# PWMFanController.net
KiCad netlist of a schematic drawn in EasyEDA Pro
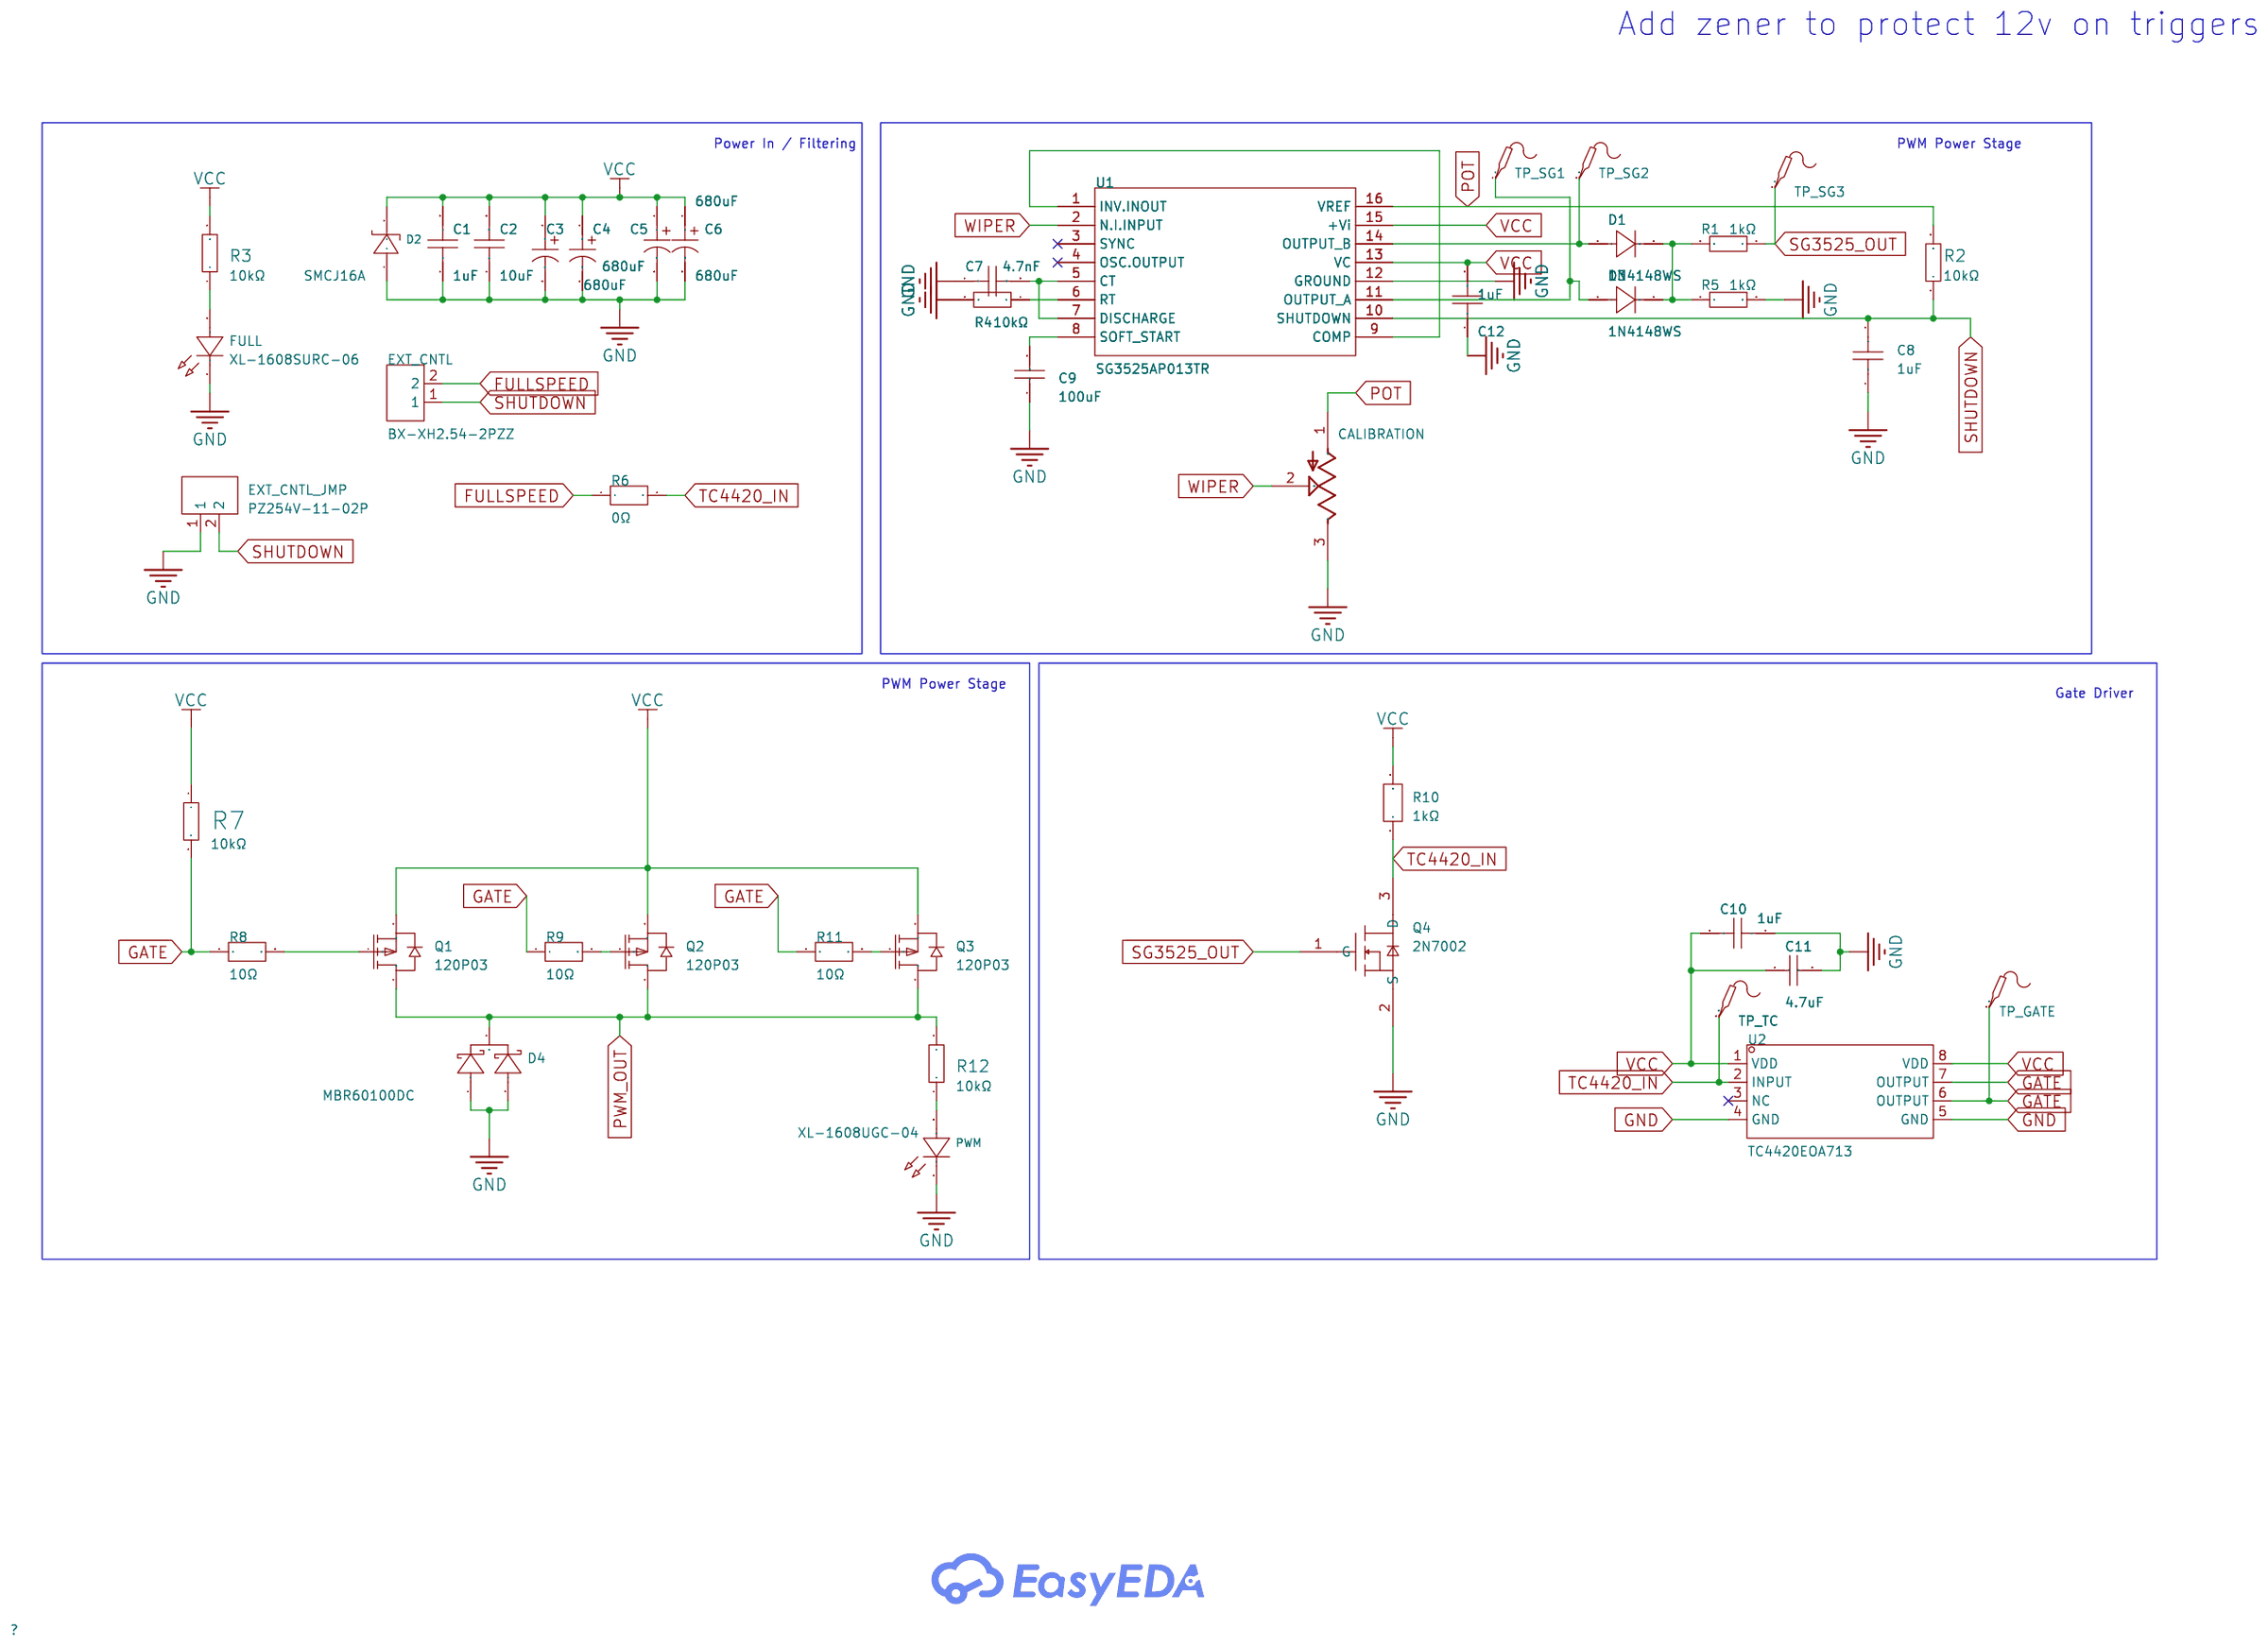
[diagram p0: schematic sheet]

(export (version "E")
  (design (tool "Eeschema 10.0.6"))
  (components
    (comp (ref "C1")
      (value "1uF")
      (footprint "easyedapro:C0805")
      (fields
        (field (name "Manufacturer Part") "GCM21BR7YA105KA55L")
        (field (name "Manufacturer") "muRata(村田)")
      )
      (libsource (lib "easyedapro") (part "GCM21BR7YA105KA55L"))
    )
    (comp (ref "C2")
      (value "10uF")
      (footprint "easyedapro:C0805")
      (fields
        (field (name "Manufacturer Part") "GRM21BC8YA106KE11L")
        (field (name "Manufacturer") "muRata(村田)")
      )
      (libsource (lib "easyedapro") (part "GRM21BC8YA106KE11L"))
    )
    (comp (ref "C3")
      (value "680uF")
      (footprint "easyedapro:CAP-SMD_BD10.0-L10.3-W10.3-FD-LS11.0_H12.0")
      (fields (field (name "Manufacturer Part") "MA35V680M10X13") (field (name "Manufacturer") "JIERR(捷而瑞)"))
      (libsource (lib "easyedapro") (part "MA35V680M10X13"))
    )
    (comp (ref "C4")
      (value "680uF")
      (footprint "easyedapro:CAP-SMD_BD10.0-L10.3-W10.3-FD-LS11.0_H12.0")
      (fields (field (name "Manufacturer Part") "MA35V680M10X13") (field (name "Manufacturer") "JIERR(捷而瑞)"))
      (libsource (lib "easyedapro") (part "MA35V680M10X13"))
    )
    (comp (ref "C5")
      (value "680uF")
      (footprint "easyedapro:CAP-SMD_BD10.0-L10.3-W10.3-FD-LS11.0_H12.0")
      (fields (field (name "Manufacturer Part") "MA35V680M10X13") (field (name "Manufacturer") "JIERR(捷而瑞)"))
      (libsource (lib "easyedapro") (part "MA35V680M10X13"))
    )
    (comp (ref "C6")
      (value "680uF")
      (footprint "easyedapro:CAP-SMD_BD10.0-L10.3-W10.3-FD-LS11.0_H12.0")
      (fields (field (name "Manufacturer Part") "MA35V680M10X13") (field (name "Manufacturer") "JIERR(捷而瑞)"))
      (libsource (lib "easyedapro") (part "MA35V680M10X13"))
    )
    (comp (ref "C7")
      (value "4.7nF")
      (footprint "easyedapro:C0603")
      (fields
        (field (name "Manufacturer Part") "CC0603JRNPO9BN472")
        (field (name "Manufacturer") "YAGEO(国巨)")
      )
      (libsource (lib "easyedapro") (part "CC0603JRNPO9BN472"))
    )
    (comp (ref "C8")
      (value "1uF")
      (footprint "easyedapro:C0603")
      (description "Capacitance:1uF Tolerance:±10% Tolerance:±10% Voltage Rating:25V Temperature Coefficient:X7R")
      (fields
        (field (name "Manufacturer Part") "HGC0603R7105K250NTHJ")
        (field (name "Manufacturer") "Chinocera(华瓷)")
      )
      (libsource (lib "easyedapro") (part "HGC0603R7105K250NTHJ"))
    )
    (comp (ref "C9")
      (value "100uF")
      (footprint "easyedapro:C1206")
      (description "Capacitance:100uF Tolerance:±20% Tolerance:±20% Voltage Rating:6.3V Temperature Coefficient:X5R")
      (fields
        (field (name "Manufacturer Part") "CL31A107MQHNNNE")
        (field (name "Manufacturer") "SAMSUNG(三星)")
      )
      (libsource (lib "easyedapro") (part "CL31A107MQHNNNE"))
    )
    (comp (ref "C10")
      (value "1uF")
      (footprint "easyedapro:C0603")
      (description "Capacitance:1uF Tolerance:±10% Tolerance:±10% Voltage Rating:35V Temperature Coefficient:X7R")
      (fields (field (name "Manufacturer Part") "CGA3E1X7R1V105KT000N") (field (name "Manufacturer") "TDK"))
      (libsource (lib "easyedapro") (part "CGA3E1X7R1V105KT000N"))
    )
    (comp (ref "C11")
      (value "4.7uF")
      (footprint "easyedapro:C0603")
      (description "Capacitance:4.7uF Tolerance:±10% Tolerance:±10% Voltage Rating:16V Temperature Coefficient:X5R")
      (fields
        (field (name "Manufacturer Part") "EMK107ABJ475KA-T")
        (field (name "Manufacturer") "TAIYO YUDEN(太诱)")
      )
      (libsource (lib "easyedapro") (part "EMK107ABJ475KA-T"))
    )
    (comp (ref "C12")
      (value "1uF")
      (footprint "easyedapro:C0603")
      (description "Capacitance:1uF Tolerance:±10% Tolerance:±10% Voltage Rating:25V Temperature Coefficient:X7R")
      (fields
        (field (name "Manufacturer Part") "HGC0603R7105K250NTHJ")
        (field (name "Manufacturer") "Chinocera(华瓷)")
      )
      (libsource (lib "easyedapro") (part "HGC0603R7105K250NTHJ"))
    )
    (comp (ref "CALIBRATION")
      (value "10kΩ")
      (description "Resistance: Tolerance:±10% Tolerance:±10%")
      (fields (field (name "Manufacturer Part") "3362P-1-103") (field (name "Manufacturer") "BOCHEN(博晨)"))
      (libsource (lib "easyedapro") (part "3362P-1-253LF_3362P-1-253LF_"))
    )
    (comp (ref "D1")
      (value "1N4148WS")
      (footprint "easyedapro:SOD-323_L1.8-W1.3-LS2.5-RD")
      (fields (field (name "Manufacturer") "JSMSEMI(杰盛微)"))
      (libsource (lib "easyedapro") (part "1N4148WS_C917117"))
    )
    (comp (ref "D2")
      (value "SMCJ16A")
      (footprint "easyedapro:SMC_L7.1-W6.2-LS8.1-R-RD")
      (fields (field (name "Manufacturer") "RUILON(瑞隆源)"))
      (libsource (lib "easyedapro") (part "SMCJ16A"))
    )
    (comp (ref "D3")
      (value "1N4148WS")
      (footprint "easyedapro:SOD-323_L1.8-W1.3-LS2.5-RD")
      (fields (field (name "Manufacturer") "JSMSEMI(杰盛微)"))
      (libsource (lib "easyedapro") (part "1N4148WS_C917117"))
    )
    (comp (ref "D4")
      (value "MBR60100DC")
      (fields (field (name "Manufacturer") "YFW(佑风微)"))
      (libsource (lib "easyedapro") (part "SBDB40100TCTB"))
    )
    (comp (ref "EXT_CNTL")
      (value "BX-XH2.54-2PZZ")
      (footprint "easyedapro:CONN-TH_2P-P2.50_BX-XH2.54-2PZZ")
      (fields (field (name "Manufacturer") "Bossie(博锡)"))
      (libsource (lib "easyedapro") (part "BX-XH2.54-2PZZ"))
    )
    (comp (ref "EXT_CNTL_JMP")
      (value "PZ254V-11-02P")
      (footprint "easyedapro:HDR-TH_2P-P2.54-V-M")
      (fields (field (name "Manufacturer") "XFCN(兴飞)"))
      (libsource (lib "easyedapro") (part "PZ254V-11-02P"))
    )
    (comp (ref "FULL")
      (value "XL-1608SURC-06")
      (footprint "easyedapro:LED0603-RD_RED")
      (fields (field (name "Manufacturer") "XINGLIGHT(成兴光)"))
      (libsource (lib "easyedapro") (part "XL-1608SURC-06"))
    )
    (comp (ref "PWM")
      (value "XL-1608UGC-04")
      (footprint "easyedapro:LED0603-RD_GREEN")
      (fields (field (name "Manufacturer") "XINGLIGHT(成兴光)"))
      (libsource (lib "easyedapro") (part "XL-1608UGC-04"))
    )
    (comp (ref "Q1")
      (value "120P03")
      (footprint "easyedapro:TO-252-2_L6.6-W6.1-P4.57-LS9.9-BR-CW")
      (fields (field (name "Manufacturer") "HL(富海微)"))
      (libsource (lib "easyedapro") (part "120P03"))
    )
    (comp (ref "Q2")
      (value "120P03")
      (footprint "easyedapro:TO-252-2_L6.6-W6.1-P4.57-LS9.9-BR-CW")
      (fields (field (name "Manufacturer") "HL(富海微)"))
      (libsource (lib "easyedapro") (part "120P03"))
    )
    (comp (ref "Q3")
      (value "120P03")
      (footprint "easyedapro:TO-252-2_L6.6-W6.1-P4.57-LS9.9-BR-CW")
      (fields (field (name "Manufacturer") "HL(富海微)"))
      (libsource (lib "easyedapro") (part "120P03"))
    )
    (comp (ref "Q4")
      (value "2N7002")
      (footprint "easyedapro:SOT-23-3_L2.9-W1.3-P1.90-LS2.4-BR")
      (fields (field (name "Manufacturer") "JSMSEMI(杰盛微)"))
      (libsource (lib "easyedapro") (part "2N7002_C916396"))
    )
    (comp (ref "R1")
      (value "1kΩ")
      (footprint "easyedapro:R0603")
      (fields
        (field (name "Manufacturer Part") "0603WAF1001T5E")
        (field (name "Manufacturer") "UNI-ROYAL(厚声)")
      )
      (libsource (lib "easyedapro") (part "0603WAF1001T5E"))
    )
    (comp (ref "R2")
      (value "10kΩ")
      (footprint "easyedapro:R0603")
      (fields
        (field (name "Manufacturer Part") "0603WAF1002T5E")
        (field (name "Manufacturer") "UNI-ROYAL(厚声)")
      )
      (libsource (lib "easyedapro") (part "0603WAF1002T5E"))
    )
    (comp (ref "R3")
      (value "10kΩ")
      (footprint "easyedapro:R0603")
      (fields
        (field (name "Manufacturer Part") "0603WAF1002T5E")
        (field (name "Manufacturer") "UNI-ROYAL(厚声)")
      )
      (libsource (lib "easyedapro") (part "0603WAF1002T5E"))
    )
    (comp (ref "R4")
      (value "10kΩ")
      (footprint "easyedapro:R0603")
      (fields
        (field (name "Manufacturer Part") "0603WAF1002T5E")
        (field (name "Manufacturer") "UNI-ROYAL(厚声)")
      )
      (libsource (lib "easyedapro") (part "0603WAF1002T5E"))
    )
    (comp (ref "R5")
      (value "1kΩ")
      (footprint "easyedapro:R0603")
      (fields
        (field (name "Manufacturer Part") "0603WAF1001T5E")
        (field (name "Manufacturer") "UNI-ROYAL(厚声)")
      )
      (libsource (lib "easyedapro") (part "0603WAF1001T5E"))
    )
    (comp (ref "R6")
      (value "0Ω")
      (footprint "easyedapro:R1210")
      (fields (field (name "Manufacturer Part") "FRC1210F0000TS") (field (name "Manufacturer") "FOJAN(富捷)"))
      (libsource (lib "easyedapro") (part "FRC1210F0000TS"))
    )
    (comp (ref "R7")
      (value "10kΩ")
      (footprint "easyedapro:R0603")
      (fields
        (field (name "Manufacturer Part") "0603WAF1002T5E")
        (field (name "Manufacturer") "UNI-ROYAL(厚声)")
      )
      (libsource (lib "easyedapro") (part "0603WAF1002T5E"))
    )
    (comp (ref "R8")
      (value "10Ω")
      (footprint "easyedapro:R0805")
      (fields
        (field (name "Manufacturer Part") "AS05W2J0100T5E")
        (field (name "Manufacturer") "UNI-ROYAL(厚声)")
      )
      (libsource (lib "easyedapro") (part "AS05W3J0100T5E"))
    )
    (comp (ref "R9")
      (value "10Ω")
      (footprint "easyedapro:R0805")
      (fields
        (field (name "Manufacturer Part") "AS05W2J0100T5E")
        (field (name "Manufacturer") "UNI-ROYAL(厚声)")
      )
      (libsource (lib "easyedapro") (part "AS05W3J0100T5E"))
    )
    (comp (ref "R10")
      (value "1kΩ")
      (footprint "easyedapro:R1210")
      (fields (field (name "Manufacturer Part") "FRC1210J102TS") (field (name "Manufacturer") "FOJAN(富捷)"))
      (libsource (lib "easyedapro") (part "FRC1210J102TS"))
    )
    (comp (ref "R11")
      (value "10Ω")
      (footprint "easyedapro:R0805")
      (fields
        (field (name "Manufacturer Part") "AS05W2J0100T5E")
        (field (name "Manufacturer") "UNI-ROYAL(厚声)")
      )
      (libsource (lib "easyedapro") (part "AS05W3J0100T5E"))
    )
    (comp (ref "R12")
      (value "10kΩ")
      (footprint "easyedapro:R0603")
      (fields
        (field (name "Manufacturer Part") "0603WAF1002T5E")
        (field (name "Manufacturer") "UNI-ROYAL(厚声)")
      )
      (libsource (lib "easyedapro") (part "0603WAF1002T5E"))
    )
    (comp (ref "TP_GATE")
      (value "~")
      (footprint "easyedapro:Test-Point-0.5mm")
      (description "Test Point 测试点")
      (libsource (lib "easyedapro") (part "Test-Point"))
    )
    (comp (ref "TP_SG1")
      (value "~")
      (footprint "easyedapro:Test-Point-0.5mm")
      (description "Test Point 测试点")
      (libsource (lib "easyedapro") (part "Test-Point"))
    )
    (comp (ref "TP_SG2")
      (value "~")
      (footprint "easyedapro:Test-Point-0.5mm")
      (description "Test Point 测试点")
      (libsource (lib "easyedapro") (part "Test-Point"))
    )
    (comp (ref "TP_SG3")
      (value "~")
      (footprint "easyedapro:Test-Point-0.5mm")
      (description "Test Point 测试点")
      (libsource (lib "easyedapro") (part "Test-Point"))
    )
    (comp (ref "TP_TC")
      (value "~")
      (footprint "easyedapro:Test-Point-0.5mm")
      (description "Test Point 测试点")
      (libsource (lib "easyedapro") (part "Test-Point"))
    )
    (comp (ref "U1")
      (value "SG3525AP013TR")
      (footprint "easyedapro:SOIC-16_L9.9-W3.9-P1.27-LS6.0-BL")
      (fields (field (name "Manufacturer") "ST(意法半导体)"))
      (libsource (lib "easyedapro") (part "SG3525AP013TR"))
    )
    (comp (ref "U2")
      (value "TC4420EOA713")
      (footprint "easyedapro:SOIC-8_L5.0-W4.0-P1.27-LS6.0-BL")
      (fields (field (name "Manufacturer") "MICROCHIP(美国微芯)"))
      (libsource (lib "easyedapro") (part "TC4420EOA713"))
    )
  )
  (nets
    (net (code "1") (name "FULLSPEED") (class "Default")
      (node (ref "EXT_CNTL") (pin "2") (pinfunction "2_2") (pintype "unspecified"))
      (node (ref "R6") (pin "1") (pinfunction "1_1") (pintype "unspecified"))
    )
    (net (code "2") (name "GATE") (class "Default")
      (node (ref "R11") (pin "1") (pinfunction "1_1") (pintype "unspecified"))
      (node (ref "R7") (pin "2") (pinfunction "2_2") (pintype "input"))
      (node (ref "R8") (pin "1") (pinfunction "1_1") (pintype "unspecified"))
      (node (ref "R9") (pin "1") (pinfunction "1_1") (pintype "unspecified"))
      (node (ref "TP_GATE") (pin "1") (pinfunction "1_1") (pintype "unspecified"))
      (node (ref "U2") (pin "6") (pinfunction "OUTPUT_6") (pintype "unspecified"))
      (node (ref "U2") (pin "7") (pinfunction "OUTPUT_7") (pintype "unspecified"))
    )
    (net (code "3") (name "GND") (class "Default")
      (node (ref "C1") (pin "1") (pinfunction "1_1") (pintype "unspecified"))
      (node (ref "C10") (pin "1") (pinfunction "1_1") (pintype "unspecified"))
      (node (ref "C11") (pin "2") (pinfunction "2_2") (pintype "input"))
      (node (ref "C12") (pin "1") (pinfunction "1_1") (pintype "unspecified"))
      (node (ref "C2") (pin "1") (pinfunction "1_1") (pintype "unspecified"))
      (node (ref "C3") (pin "2") (pinfunction "2_2") (pintype "input"))
      (node (ref "C4") (pin "2") (pinfunction "2_2") (pintype "input"))
      (node (ref "C5") (pin "2") (pinfunction "2_2") (pintype "input"))
      (node (ref "C6") (pin "2") (pinfunction "2_2") (pintype "input"))
      (node (ref "C7") (pin "1") (pinfunction "1_1") (pintype "input"))
      (node (ref "C8") (pin "1") (pinfunction "1_1") (pintype "unspecified"))
      (node (ref "C9") (pin "1") (pinfunction "1_1") (pintype "input"))
      (node (ref "CALIBRATION") (pin "3") (pinfunction "CW_3") (pintype "unspecified"))
      (node (ref "D2") (pin "1") (pinfunction "A_1") (pintype "input"))
      (node (ref "D4") (pin "1") (pinfunction "A_1") (pintype "unspecified"))
      (node (ref "D4") (pin "3") (pinfunction "A_3") (pintype "unspecified"))
      (node (ref "EXT_CNTL_JMP") (pin "1") (pinfunction "1_1") (pintype "unspecified"))
      (node (ref "FULL") (pin "1") (pinfunction "K_1") (pintype "unspecified"))
      (node (ref "PWM") (pin "1") (pinfunction "K_1") (pintype "input"))
      (node (ref "Q4") (pin "2") (pinfunction "S_2") (pintype "unspecified"))
      (node (ref "R4") (pin "2") (pinfunction "2_2") (pintype "input"))
      (node (ref "R5") (pin "2") (pinfunction "2_2") (pintype "input"))
      (node (ref "U1") (pin "12") (pinfunction "GROUND_12") (pintype "unspecified"))
      (node (ref "U2") (pin "4") (pinfunction "GND_4") (pintype "unspecified"))
      (node (ref "U2") (pin "5") (pinfunction "GND_5") (pintype "unspecified"))
    )
    (net (code "4") (name "Net-(D1-A)") (class "Default")
      (node (ref "D1") (pin "2") (pinfunction "A_2") (pintype "unspecified"))
      (node (ref "TP_SG2") (pin "1") (pinfunction "1_1") (pintype "unspecified"))
      (node (ref "U1") (pin "14") (pinfunction "OUTPUT_B_14") (pintype "unspecified"))
    )
    (net (code "5") (name "Net-(D1-C)") (class "Default")
      (node (ref "D1") (pin "1") (pinfunction "C_1") (pintype "unspecified"))
      (node (ref "D3") (pin "1") (pinfunction "C_1") (pintype "unspecified"))
      (node (ref "R1") (pin "2") (pinfunction "2_2") (pintype "input"))
      (node (ref "R5") (pin "1") (pinfunction "1_1") (pintype "input"))
    )
    (net (code "6") (name "Net-(D3-A)") (class "Default")
      (node (ref "D3") (pin "2") (pinfunction "A_2") (pintype "unspecified"))
      (node (ref "TP_SG1") (pin "1") (pinfunction "1_1") (pintype "unspecified"))
      (node (ref "U1") (pin "11") (pinfunction "OUTPUT_A_11") (pintype "unspecified"))
    )
    (net (code "7") (name "Net-(FULL-A)") (class "Default")
      (node (ref "FULL") (pin "2") (pinfunction "A_2") (pintype "unspecified"))
      (node (ref "R3") (pin "1") (pinfunction "1_1") (pintype "input"))
    )
    (net (code "8") (name "Net-(PWM-A)") (class "Default")
      (node (ref "PWM") (pin "2") (pinfunction "A_2") (pintype "input"))
      (node (ref "R12") (pin "1") (pinfunction "1_1") (pintype "input"))
    )
    (net (code "9") (name "Net-(Q1-G)") (class "Default")
      (node (ref "Q1") (pin "1") (pinfunction "G_1") (pintype "unspecified"))
      (node (ref "R8") (pin "2") (pinfunction "2_2") (pintype "unspecified"))
    )
    (net (code "10") (name "Net-(Q2-G)") (class "Default")
      (node (ref "Q2") (pin "1") (pinfunction "G_1") (pintype "unspecified"))
      (node (ref "R9") (pin "2") (pinfunction "2_2") (pintype "unspecified"))
    )
    (net (code "11") (name "Net-(Q3-G)") (class "Default")
      (node (ref "Q3") (pin "1") (pinfunction "G_1") (pintype "unspecified"))
      (node (ref "R11") (pin "2") (pinfunction "2_2") (pintype "unspecified"))
    )
    (net (code "12") (name "Net-(U1-COMP)") (class "Default")
      (node (ref "U1") (pin "1") (pinfunction "INV.INOUT_1") (pintype "unspecified"))
      (node (ref "U1") (pin "9") (pinfunction "COMP_9") (pintype "unspecified"))
    )
    (net (code "13") (name "Net-(U1-CT)") (class "Default")
      (node (ref "C7") (pin "2") (pinfunction "2_2") (pintype "input"))
      (node (ref "U1") (pin "5") (pinfunction "CT_5") (pintype "unspecified"))
      (node (ref "U1") (pin "7") (pinfunction "DISCHARGE_7") (pintype "unspecified"))
    )
    (net (code "14") (name "Net-(U1-RT)") (class "Default")
      (node (ref "R4") (pin "1") (pinfunction "1_1") (pintype "input"))
      (node (ref "U1") (pin "6") (pinfunction "RT_6") (pintype "unspecified"))
    )
    (net (code "15") (name "Net-(U1-SOFT_START)") (class "Default")
      (node (ref "C9") (pin "2") (pinfunction "2_2") (pintype "input"))
      (node (ref "U1") (pin "8") (pinfunction "SOFT_START_8") (pintype "unspecified"))
    )
    (net (code "16") (name "POT") (class "Default")
      (node (ref "CALIBRATION") (pin "1") (pinfunction "CCW_1") (pintype "unspecified"))
      (node (ref "R2") (pin "2") (pinfunction "2_2") (pintype "input"))
      (node (ref "U1") (pin "16") (pinfunction "VREF_16") (pintype "unspecified"))
    )
    (net (code "17") (name "PWM_OUT") (class "Default")
      (node (ref "D4") (pin "2") (pinfunction "C_2") (pintype "unspecified"))
      (node (ref "Q1") (pin "2") (pinfunction "D_2") (pintype "unspecified"))
      (node (ref "Q2") (pin "2") (pinfunction "D_2") (pintype "unspecified"))
      (node (ref "Q3") (pin "2") (pinfunction "D_2") (pintype "unspecified"))
      (node (ref "R12") (pin "2") (pinfunction "2_2") (pintype "input"))
    )
    (net (code "18") (name "SG3525_OUT") (class "Default")
      (node (ref "Q4") (pin "1") (pinfunction "G_1") (pintype "unspecified"))
      (node (ref "R1") (pin "1") (pinfunction "1_1") (pintype "input"))
      (node (ref "TP_SG3") (pin "1") (pinfunction "1_1") (pintype "unspecified"))
    )
    (net (code "19") (name "SHUTDOWN") (class "Default")
      (node (ref "C8") (pin "2") (pinfunction "2_2") (pintype "unspecified"))
      (node (ref "EXT_CNTL") (pin "1") (pinfunction "1_1") (pintype "unspecified"))
      (node (ref "EXT_CNTL_JMP") (pin "2") (pinfunction "2_2") (pintype "unspecified"))
      (node (ref "R2") (pin "1") (pinfunction "1_1") (pintype "input"))
      (node (ref "U1") (pin "10") (pinfunction "SHUTDOWN_10") (pintype "unspecified"))
    )
    (net (code "20") (name "TC4420_IN") (class "Default")
      (node (ref "Q4") (pin "3") (pinfunction "D_3") (pintype "unspecified"))
      (node (ref "R10") (pin "1") (pinfunction "1_1") (pintype "unspecified"))
      (node (ref "R6") (pin "2") (pinfunction "2_2") (pintype "unspecified"))
      (node (ref "TP_TC") (pin "1") (pinfunction "1_1") (pintype "unspecified"))
      (node (ref "U2") (pin "2") (pinfunction "INPUT_2") (pintype "unspecified"))
    )
    (net (code "21") (name "VCC") (class "Default")
      (node (ref "C1") (pin "2") (pinfunction "2_2") (pintype "unspecified"))
      (node (ref "C10") (pin "2") (pinfunction "2_2") (pintype "unspecified"))
      (node (ref "C11") (pin "1") (pinfunction "1_1") (pintype "input"))
      (node (ref "C12") (pin "2") (pinfunction "2_2") (pintype "unspecified"))
      (node (ref "C2") (pin "2") (pinfunction "2_2") (pintype "unspecified"))
      (node (ref "C3") (pin "1") (pinfunction "1_1") (pintype "input"))
      (node (ref "C4") (pin "1") (pinfunction "1_1") (pintype "input"))
      (node (ref "C5") (pin "1") (pinfunction "1_1") (pintype "input"))
      (node (ref "C6") (pin "1") (pinfunction "1_1") (pintype "input"))
      (node (ref "D2") (pin "2") (pinfunction "K_2") (pintype "input"))
      (node (ref "Q1") (pin "3") (pinfunction "S_3") (pintype "unspecified"))
      (node (ref "Q2") (pin "3") (pinfunction "S_3") (pintype "unspecified"))
      (node (ref "Q3") (pin "3") (pinfunction "S_3") (pintype "unspecified"))
      (node (ref "R10") (pin "2") (pinfunction "2_2") (pintype "unspecified"))
      (node (ref "R3") (pin "2") (pinfunction "2_2") (pintype "input"))
      (node (ref "R7") (pin "1") (pinfunction "1_1") (pintype "input"))
      (node (ref "U1") (pin "13") (pinfunction "VC_13") (pintype "unspecified"))
      (node (ref "U1") (pin "15") (pinfunction "+Vi_15") (pintype "unspecified"))
      (node (ref "U2") (pin "1") (pinfunction "VDD_1") (pintype "unspecified"))
      (node (ref "U2") (pin "8") (pinfunction "VDD_8") (pintype "unspecified"))
    )
    (net (code "22") (name "WIPER") (class "Default")
      (node (ref "CALIBRATION") (pin "2") (pinfunction "WIPER_2") (pintype "unspecified"))
      (node (ref "U1") (pin "2") (pinfunction "N.I.INPUT_2") (pintype "unspecified"))
    )
    (net (code "23") (name "unconnected-(U1-OSC.OUTPUT-Pad4)") (class "Default")
      (node (ref "U1") (pin "4") (pinfunction "OSC.OUTPUT_4") (pintype "unspecified+no_connect"))
    )
    (net (code "24") (name "unconnected-(U1-SYNC-Pad3)") (class "Default")
      (node (ref "U1") (pin "3") (pinfunction "SYNC_3") (pintype "unspecified+no_connect"))
    )
    (net (code "25") (name "unconnected-(U2-NC-Pad3)") (class "Default")
      (node (ref "U2") (pin "3") (pinfunction "NC_3") (pintype "unspecified+no_connect"))
    )
  )
)
